# power-clk.net
KiCad netlist of a schematic drawn in Altium Designer
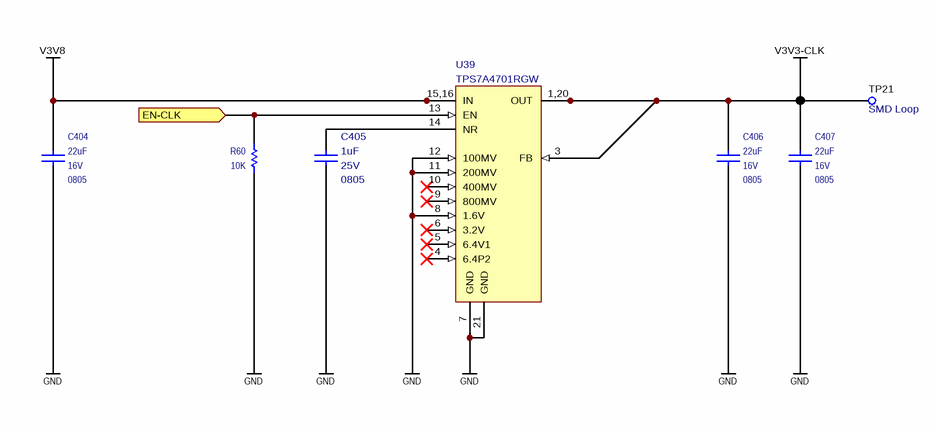
[diagram p0: power-clk.SchDoc]

(export (version "E")
  (design (tool "Eeschema 10.0.6"))
  (components
    (comp (ref "C404")
      (value "22uF")
      (footprint "generic:CAPC200X125X145L45N")
      (description "Ceramic Capacitor 22uF ±10% 16V X5R 0805")
      (fields
        (field (name "MANUFACTURER") "Samsung")
        (field (name "VOLTAGE") "16V")
        (field (name "PACKAGE") "0805")
        (field (name "TOLERANCE") "±10%")
      )
      (libsource (lib "generic") (part "CAP 0603"))
    )
    (comp (ref "C405")
      (value "1uF")
      (footprint "CAPC200X125X145L45N")
      (description "Ceramic Capacitor 1uF ±10% 25V X7R 0805")
      (fields
        (field (name "MANUFACTURER") "Taiyo Yuden")
        (field (name "TOLERANCE") "±10%")
        (field (name "PACKAGE") "0805")
        (field (name "VOLTAGE") "25V")
      )
      (libsource (lib "capacitors") (part "CAP"))
    )
    (comp (ref "C406")
      (value "22uF")
      (footprint "generic:CAPC200X125X145L45N")
      (description "Ceramic Capacitor 22uF ±10% 16V X5R 0805")
      (fields
        (field (name "MANUFACTURER") "Samsung")
        (field (name "VOLTAGE") "16V")
        (field (name "PACKAGE") "0805")
        (field (name "TOLERANCE") "±10%")
      )
      (libsource (lib "generic") (part "CAP 0603"))
    )
    (comp (ref "C407")
      (value "22uF")
      (footprint "generic:CAPC200X125X145L45N")
      (description "Ceramic Capacitor 22uF ±10% 16V X5R 0805")
      (fields
        (field (name "MANUFACTURER") "Samsung")
        (field (name "VOLTAGE") "16V")
        (field (name "PACKAGE") "0805")
        (field (name "TOLERANCE") "±10%")
      )
      (libsource (lib "generic") (part "CAP 0603"))
    )
    (comp (ref "R60")
      (value "10K")
      (footprint "RESC1005X40N")
      (description "Thick Film Resistor 10k ±1% 0.1W 50V 0402")
      (fields (field (name "MANUFACTURER") "Panasonic") (field (name "TOLERANCE") "±1%"))
      (libsource (lib "Graviton") (part "RES 0402"))
    )
    (comp (ref "TP21")
      (value "5015")
      (footprint "keystone:5015")
      (description "Test Point SMD")
      (fields (field (name "MANUFACTURER") "Keystone") (field (name "NOTES") "SMD Loop"))
      (libsource (lib "generic") (part "TEST_POINT_SMD_50"))
    )
    (comp (ref "U39")
      (value "TPS7A4701RGW")
      (footprint "QFN65P500X500X100-21N")
      (description "Low-Dropout Linear Regulator 20-VQFN")
      (fields (field (name "MANUFACTURER") "Texas Instruments"))
      (libsource (lib "ti") (part "TPS7A4701RGW_1"))
    )
  )
  (nets
    (net (code "1") (name "/EN-CLK") (class "Default")
      (node (ref "R60") (pin "1") (pinfunction "1_1") (pintype "passive"))
      (node (ref "U39") (pin "13") (pinfunction "EN_13") (pintype "input"))
    )
    (net (code "2") (name "GND") (class "Default")
      (node (ref "C404") (pin "1") (pinfunction "1_1") (pintype "passive"))
      (node (ref "C405") (pin "2") (pinfunction "2_2") (pintype "passive"))
      (node (ref "C406") (pin "1") (pinfunction "1_1") (pintype "passive"))
      (node (ref "C407") (pin "1") (pinfunction "1_1") (pintype "passive"))
      (node (ref "R60") (pin "2") (pinfunction "2_2") (pintype "passive"))
      (node (ref "U39") (pin "11") (pinfunction "200MV_11") (pintype "input"))
      (node (ref "U39") (pin "12") (pinfunction "100MV_12") (pintype "input"))
      (node (ref "U39") (pin "21") (pinfunction "GND_21") (pintype "power_in"))
      (node (ref "U39") (pin "7") (pinfunction "GND_7") (pintype "power_in"))
      (node (ref "U39") (pin "8") (pinfunction "1.6V_8") (pintype "input"))
    )
    (net (code "3") (name "Net-(U39-NR)") (class "Default")
      (node (ref "C405") (pin "1") (pinfunction "1_1") (pintype "passive"))
      (node (ref "U39") (pin "14") (pinfunction "NR_14") (pintype "passive"))
    )
    (net (code "4") (name "V3V3-CLK") (class "Default")
      (node (ref "C406") (pin "2") (pinfunction "2_2") (pintype "passive"))
      (node (ref "C407") (pin "2") (pinfunction "2_2") (pintype "passive"))
      (node (ref "TP21") (pin "1") (pinfunction "1_1") (pintype "passive"))
      (node (ref "U39") (pin "1") (pinfunction "OUT_1") (pintype "passive"))
      (node (ref "U39") (pin "20") (pinfunction "OUT_20") (pintype "passive"))
      (node (ref "U39") (pin "3") (pinfunction "FB_3") (pintype "input"))
    )
    (net (code "5") (name "V3V8") (class "Default")
      (node (ref "C404") (pin "2") (pinfunction "2_2") (pintype "passive"))
      (node (ref "U39") (pin "15") (pinfunction "IN_15") (pintype "passive"))
      (node (ref "U39") (pin "16") (pinfunction "IN_16") (pintype "passive"))
    )
    (net (code "6") (name "unconnected-(U39-3.2V-Pad6)") (class "Default")
      (node (ref "U39") (pin "6") (pinfunction "3.2V_6") (pintype "input+no_connect"))
    )
    (net (code "7") (name "unconnected-(U39-6.4P2-Pad4)") (class "Default")
      (node (ref "U39") (pin "4") (pinfunction "6.4P2_4") (pintype "input+no_connect"))
    )
    (net (code "8") (name "unconnected-(U39-6.4V1-Pad5)") (class "Default")
      (node (ref "U39") (pin "5") (pinfunction "6.4V1_5") (pintype "input+no_connect"))
    )
    (net (code "9") (name "unconnected-(U39-400MV-Pad10)") (class "Default")
      (node (ref "U39") (pin "10") (pinfunction "400MV_10") (pintype "input+no_connect"))
    )
    (net (code "10") (name "unconnected-(U39-800MV-Pad9)") (class "Default")
      (node (ref "U39") (pin "9") (pinfunction "800MV_9") (pintype "input+no_connect"))
    )
  )
)
